# LED_current_source_buffer_only.net
KiCad netlist of a schematic drawn in EAGLE
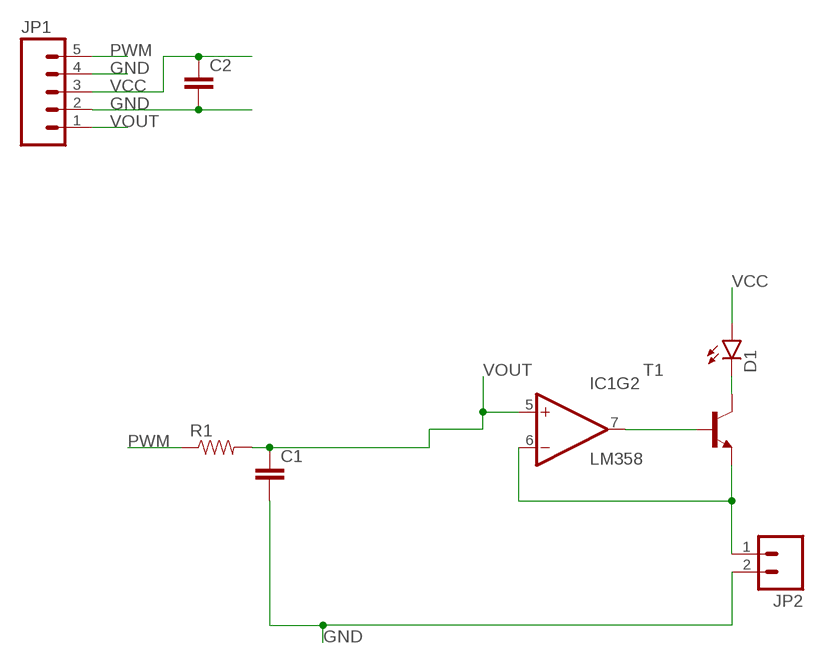
[diagram p0: schematic, sheet 1]

(export (version "E")
  (design (tool "Eeschema 10.0.6"))
  (components
    (comp (ref "C1")
      (value "CAP0603-CAP")
      (footprint "eagle-import:0603-CAP")
      (libsource (lib "eagle-import") (part "CAP0603-CAP"))
    )
    (comp (ref "C2")
      (value "CAP0603-CAP")
      (footprint "eagle-import:0603-CAP")
      (libsource (lib "eagle-import") (part "CAP0603-CAP"))
    )
    (comp (ref "D1")
      (value "LED5MM")
      (footprint "eagle-import:LED5MM")
      (libsource (lib "eagle-import") (part "LED5MM"))
    )
    (comp (ref "IC1")
      (value "LM358")
      (footprint "eagle-import:DIP08")
      (libsource (lib "eagle-import") (part "LM358"))
    )
    (comp (ref "JP1")
      (value "M05PTH")
      (footprint "eagle-import:1X05")
      (libsource (lib "eagle-import") (part "M05PTH"))
    )
    (comp (ref "JP2")
      (value "M02PTH")
      (footprint "eagle-import:1X02")
      (libsource (lib "eagle-import") (part "M02PTH"))
    )
    (comp (ref "R1")
      (value "RESISTOR0603-RES")
      (footprint "eagle-import:0603-RES")
      (libsource (lib "eagle-import") (part "RESISTOR0603-RES"))
    )
    (comp (ref "T1")
      (value "2N2222-NPN-TO92-EBC")
      (footprint "eagle-import:TO92-EBC")
      (libsource (lib "eagle-import") (part "-NPN-TO92-EBC2N2222"))
    )
  )
  (nets
    (net (code "1") (name "/GND") (class "Default")
      (node (ref "C1") (pin "2") (pinfunction "2_2") (pintype "passive"))
      (node (ref "C2") (pin "2") (pinfunction "2_2") (pintype "passive"))
      (node (ref "JP1") (pin "2") (pinfunction "2_2") (pintype "passive"))
      (node (ref "JP1") (pin "4") (pinfunction "4_4") (pintype "passive"))
      (node (ref "JP2") (pin "2") (pinfunction "2_2") (pintype "passive"))
    )
    (net (code "2") (name "/PWM") (class "Default")
      (node (ref "JP1") (pin "5") (pinfunction "5_5") (pintype "passive"))
      (node (ref "R1") (pin "1") (pinfunction "1_1") (pintype "passive"))
    )
    (net (code "3") (name "/VCC") (class "Default")
      (node (ref "C2") (pin "1") (pinfunction "1_1") (pintype "passive"))
      (node (ref "D1") (pin "A") (pinfunction "A_A") (pintype "passive"))
      (node (ref "JP1") (pin "3") (pinfunction "3_3") (pintype "passive"))
    )
    (net (code "4") (name "/VOUT") (class "Default")
      (node (ref "C1") (pin "1") (pinfunction "1_1") (pintype "passive"))
      (node (ref "IC1") (pin "5") (pinfunction "+IN_5") (pintype "input"))
      (node (ref "JP1") (pin "1") (pinfunction "1_1") (pintype "passive"))
      (node (ref "R1") (pin "2") (pinfunction "2_2") (pintype "passive"))
    )
    (net (code "5") (name "Net-(D1-C)") (class "Default")
      (node (ref "D1") (pin "K") (pinfunction "C_K") (pintype "passive"))
      (node (ref "T1") (pin "C") (pinfunction "C_C") (pintype "passive"))
    )
    (net (code "6") (name "Net-(IC1B--IN)") (class "Default")
      (node (ref "IC1") (pin "6") (pinfunction "-IN_6") (pintype "input"))
      (node (ref "JP2") (pin "1") (pinfunction "1_1") (pintype "passive"))
      (node (ref "T1") (pin "E") (pinfunction "E_E") (pintype "passive"))
    )
    (net (code "7") (name "Net-(IC1B-OUT)") (class "Default")
      (node (ref "IC1") (pin "7") (pinfunction "OUT_7") (pintype "output"))
      (node (ref "T1") (pin "B") (pinfunction "B_B") (pintype "passive"))
    )
  )
)
